# MODULO2_pp.net
KiCad netlist of a schematic drawn in EAGLE
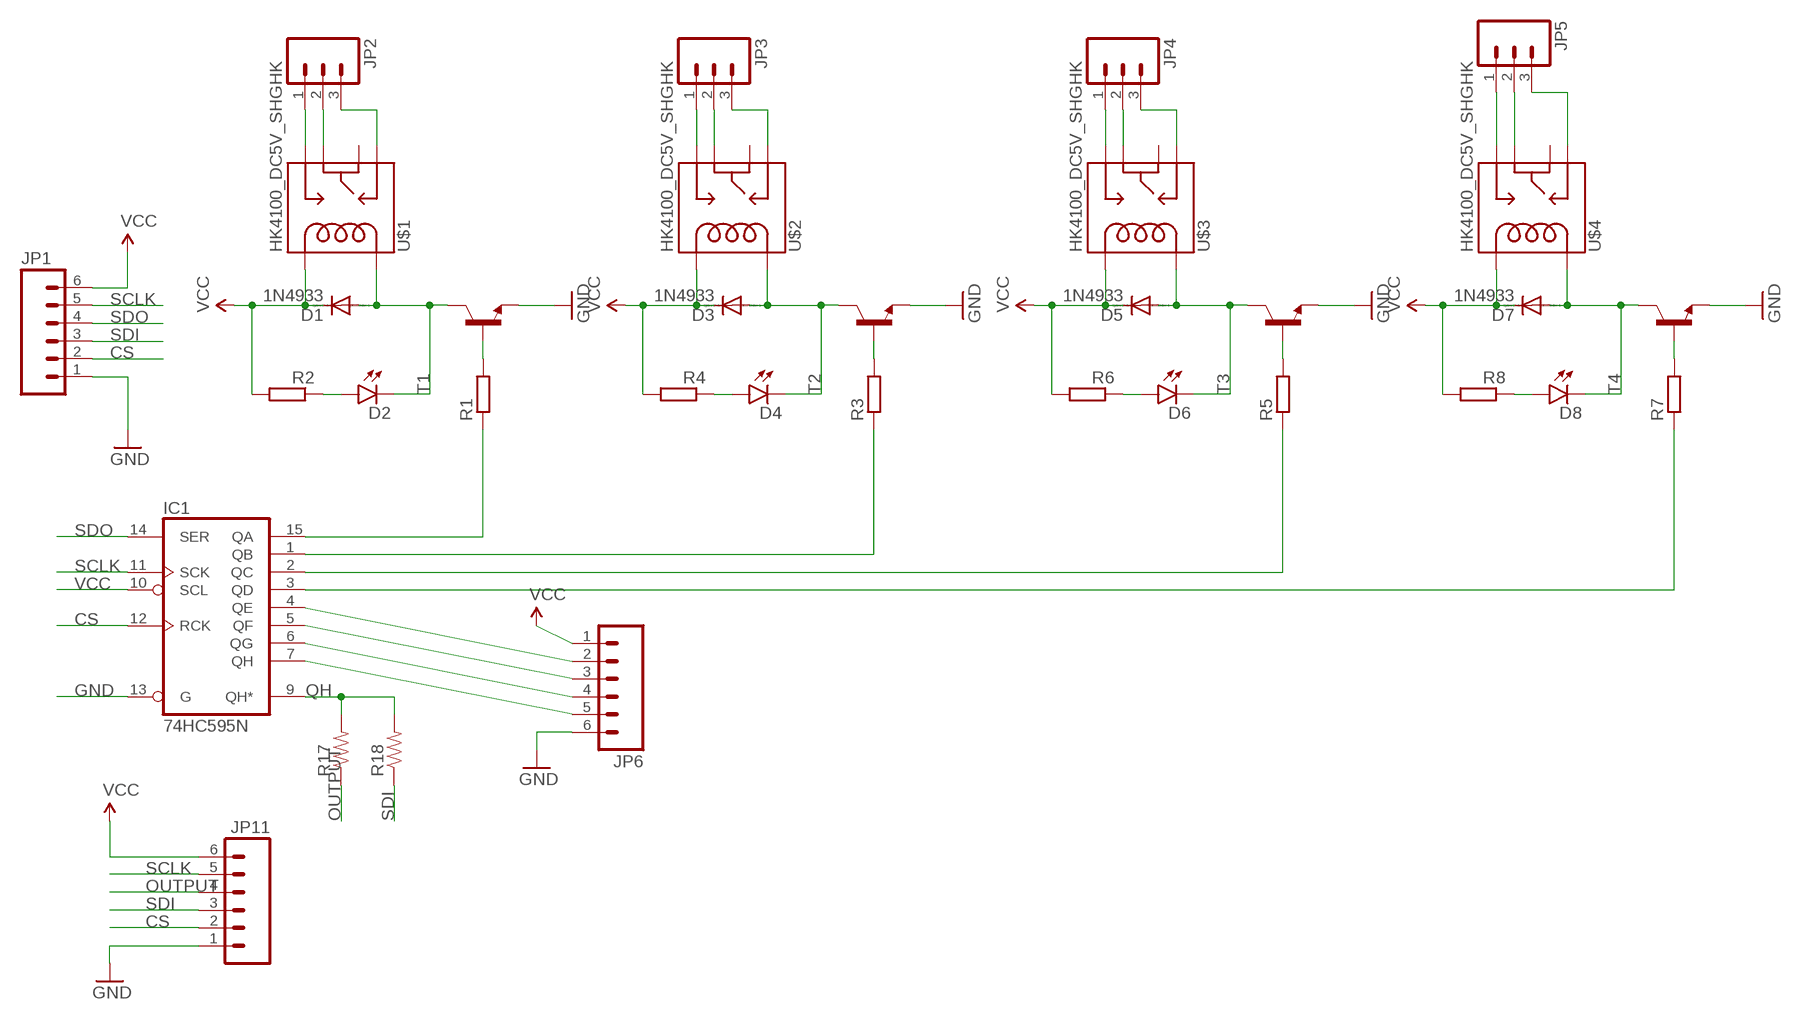
[diagram p0: schematic, sheet 1]

(export (version "E")
  (design (tool "Eeschema 10.0.6"))
  (components
    (comp (ref "D1")
      (value "1N4933")
      (footprint "eagle-import:DO41-10")
      (libsource (lib "eagle-import") (part "1N4933"))
    )
    (comp (ref "D2")
      (value "LED5MM")
      (footprint "eagle-import:LED5MM")
      (libsource (lib "eagle-import") (part "LED5MM"))
    )
    (comp (ref "D3")
      (value "1N4933")
      (footprint "eagle-import:DO41-10")
      (libsource (lib "eagle-import") (part "1N4933"))
    )
    (comp (ref "D4")
      (value "LED5MM")
      (footprint "eagle-import:LED5MM")
      (libsource (lib "eagle-import") (part "LED5MM"))
    )
    (comp (ref "D5")
      (value "1N4933")
      (footprint "eagle-import:DO41-10")
      (libsource (lib "eagle-import") (part "1N4933"))
    )
    (comp (ref "D6")
      (value "LED5MM")
      (footprint "eagle-import:LED5MM")
      (libsource (lib "eagle-import") (part "LED5MM"))
    )
    (comp (ref "D7")
      (value "1N4933")
      (footprint "eagle-import:DO41-10")
      (libsource (lib "eagle-import") (part "1N4933"))
    )
    (comp (ref "D8")
      (value "LED5MM")
      (footprint "eagle-import:LED5MM")
      (libsource (lib "eagle-import") (part "LED5MM"))
    )
    (comp (ref "IC1")
      (value "74HC595N")
      (footprint "eagle-import:DIL16")
      (libsource (lib "eagle-import") (part "74595NHC"))
    )
    (comp (ref "JP1")
      (value "M06SILK_FEMALE_PTH")
      (footprint "eagle-import:1X06")
      (libsource (lib "eagle-import") (part "M06SILK_FEMALE_PTH"))
    )
    (comp (ref "JP2")
      (value "M03-SCREW-5MM")
      (footprint "eagle-import:SCREWTERMINAL-5MM-3")
      (libsource (lib "eagle-import") (part "M03-SCREW-5MM"))
    )
    (comp (ref "JP3")
      (value "M03-SCREW-5MM")
      (footprint "eagle-import:SCREWTERMINAL-5MM-3")
      (libsource (lib "eagle-import") (part "M03-SCREW-5MM"))
    )
    (comp (ref "JP4")
      (value "M03-SCREW-5MM")
      (footprint "eagle-import:SCREWTERMINAL-5MM-3")
      (libsource (lib "eagle-import") (part "M03-SCREW-5MM"))
    )
    (comp (ref "JP5")
      (value "M03-SCREW-5MM")
      (footprint "eagle-import:SCREWTERMINAL-5MM-3")
      (libsource (lib "eagle-import") (part "M03-SCREW-5MM"))
    )
    (comp (ref "JP6")
      (value "M06SILK_FEMALE_PTH")
      (footprint "eagle-import:1X06")
      (libsource (lib "eagle-import") (part "M06SILK_FEMALE_PTH"))
    )
    (comp (ref "JP11")
      (value "M06SILK_FEMALE_PTH")
      (footprint "eagle-import:1X06")
      (libsource (lib "eagle-import") (part "M06SILK_FEMALE_PTH"))
    )
    (comp (ref "R1")
      (value "R-EU_R0805")
      (footprint "eagle-import:R0805")
      (libsource (lib "eagle-import") (part "R-EU_R0805"))
    )
    (comp (ref "R2")
      (value "R-EU_R0805")
      (footprint "eagle-import:R0805")
      (libsource (lib "eagle-import") (part "R-EU_R0805"))
    )
    (comp (ref "R3")
      (value "R-EU_R0805")
      (footprint "eagle-import:R0805")
      (libsource (lib "eagle-import") (part "R-EU_R0805"))
    )
    (comp (ref "R4")
      (value "R-EU_R0805")
      (footprint "eagle-import:R0805")
      (libsource (lib "eagle-import") (part "R-EU_R0805"))
    )
    (comp (ref "R5")
      (value "R-EU_R0805")
      (footprint "eagle-import:R0805")
      (libsource (lib "eagle-import") (part "R-EU_R0805"))
    )
    (comp (ref "R6")
      (value "R-EU_R0805")
      (footprint "eagle-import:R0805")
      (libsource (lib "eagle-import") (part "R-EU_R0805"))
    )
    (comp (ref "R7")
      (value "R-EU_R0805")
      (footprint "eagle-import:R0805")
      (libsource (lib "eagle-import") (part "R-EU_R0805"))
    )
    (comp (ref "R8")
      (value "R-EU_R0805")
      (footprint "eagle-import:R0805")
      (libsource (lib "eagle-import") (part "R-EU_R0805"))
    )
    (comp (ref "R17")
      (value "RESISTOR0805-RES")
      (footprint "eagle-import:0805")
      (libsource (lib "eagle-import") (part "RESISTOR0805-RES"))
    )
    (comp (ref "R18")
      (value "RESISTOR0805-RES")
      (footprint "eagle-import:0805")
      (libsource (lib "eagle-import") (part "RESISTOR0805-RES"))
    )
    (comp (ref "T1")
      (value "-NPN-TO92-EBC")
      (footprint "eagle-import:TO92-EBC")
      (libsource (lib "eagle-import") (part "-NPN-TO92-EBC"))
    )
    (comp (ref "T2")
      (value "-NPN-TO92-EBC")
      (footprint "eagle-import:TO92-EBC")
      (libsource (lib "eagle-import") (part "-NPN-TO92-EBC"))
    )
    (comp (ref "T3")
      (value "-NPN-TO92-EBC")
      (footprint "eagle-import:TO92-EBC")
      (libsource (lib "eagle-import") (part "-NPN-TO92-EBC"))
    )
    (comp (ref "T4")
      (value "-NPN-TO92-EBC")
      (footprint "eagle-import:TO92-EBC")
      (libsource (lib "eagle-import") (part "-NPN-TO92-EBC"))
    )
    (comp (ref "U$1")
      (value "HK4100_DC5V_SHGHK")
      (footprint "eagle-import:HK4100")
      (libsource (lib "eagle-import") (part "HK4100_DC5V_SHGHK"))
    )
    (comp (ref "U$2")
      (value "HK4100_DC5V_SHGHK")
      (footprint "eagle-import:HK4100")
      (libsource (lib "eagle-import") (part "HK4100_DC5V_SHGHK"))
    )
    (comp (ref "U$3")
      (value "HK4100_DC5V_SHGHK")
      (footprint "eagle-import:HK4100")
      (libsource (lib "eagle-import") (part "HK4100_DC5V_SHGHK"))
    )
    (comp (ref "U$4")
      (value "HK4100_DC5V_SHGHK")
      (footprint "eagle-import:HK4100")
      (libsource (lib "eagle-import") (part "HK4100_DC5V_SHGHK"))
    )
  )
  (nets
    (net (code "1") (name "/CS") (class "Default")
      (node (ref "IC1") (pin "12") (pinfunction "RCK_12") (pintype "input"))
      (node (ref "JP1") (pin "2") (pinfunction "2_2") (pintype "passive"))
      (node (ref "JP11") (pin "2") (pinfunction "2_2") (pintype "passive"))
    )
    (net (code "2") (name "/OUTPUT") (class "Default")
      (node (ref "JP11") (pin "4") (pinfunction "4_4") (pintype "passive"))
      (node (ref "R17") (pin "1") (pinfunction "1_1") (pintype "passive"))
    )
    (net (code "3") (name "/QH") (class "Default")
      (node (ref "IC1") (pin "9") (pinfunction "QH*_9") (pintype "tri_state"))
      (node (ref "R17") (pin "2") (pinfunction "2_2") (pintype "passive"))
      (node (ref "R18") (pin "2") (pinfunction "2_2") (pintype "passive"))
    )
    (net (code "4") (name "/SCLK") (class "Default")
      (node (ref "IC1") (pin "11") (pinfunction "SCK_11") (pintype "input"))
      (node (ref "JP1") (pin "5") (pinfunction "5_5") (pintype "passive"))
      (node (ref "JP11") (pin "5") (pinfunction "5_5") (pintype "passive"))
    )
    (net (code "5") (name "/SDI") (class "Default")
      (node (ref "JP1") (pin "3") (pinfunction "3_3") (pintype "passive"))
      (node (ref "JP11") (pin "3") (pinfunction "3_3") (pintype "passive"))
      (node (ref "R18") (pin "1") (pinfunction "1_1") (pintype "passive"))
    )
    (net (code "6") (name "/SDO") (class "Default")
      (node (ref "IC1") (pin "14") (pinfunction "SER_14") (pintype "input"))
      (node (ref "JP1") (pin "4") (pinfunction "4_4") (pintype "passive"))
    )
    (net (code "7") (name "GND") (class "Default")
      (node (ref "IC1") (pin "13") (pinfunction "G_13") (pintype "input"))
      (node (ref "JP1") (pin "1") (pinfunction "1_1") (pintype "passive"))
      (node (ref "JP11") (pin "1") (pinfunction "1_1") (pintype "passive"))
      (node (ref "JP6") (pin "6") (pinfunction "6_6") (pintype "passive"))
      (node (ref "T1") (pin "E") (pinfunction "E_E") (pintype "passive"))
      (node (ref "T2") (pin "E") (pinfunction "E_E") (pintype "passive"))
      (node (ref "T3") (pin "E") (pinfunction "E_E") (pintype "passive"))
      (node (ref "T4") (pin "E") (pinfunction "E_E") (pintype "passive"))
    )
    (net (code "8") (name "Net-(D2-C)") (class "Default")
      (node (ref "D1") (pin "A") (pinfunction "A_A") (pintype "passive"))
      (node (ref "D2") (pin "K") (pinfunction "C_K") (pintype "passive"))
      (node (ref "T1") (pin "C") (pinfunction "C_C") (pintype "passive"))
      (node (ref "U$1") (pin "6") (pinfunction "2_6") (pintype "bidirectional"))
    )
    (net (code "9") (name "Net-(D2-PadA)") (class "Default")
      (node (ref "D2") (pin "A") (pinfunction "A_A") (pintype "passive"))
      (node (ref "R2") (pin "1") (pinfunction "1_1") (pintype "passive"))
    )
    (net (code "10") (name "Net-(D4-C)") (class "Default")
      (node (ref "D3") (pin "A") (pinfunction "A_A") (pintype "passive"))
      (node (ref "D4") (pin "K") (pinfunction "C_K") (pintype "passive"))
      (node (ref "T2") (pin "C") (pinfunction "C_C") (pintype "passive"))
      (node (ref "U$2") (pin "6") (pinfunction "2_6") (pintype "bidirectional"))
    )
    (net (code "11") (name "Net-(D4-PadA)") (class "Default")
      (node (ref "D4") (pin "A") (pinfunction "A_A") (pintype "passive"))
      (node (ref "R4") (pin "1") (pinfunction "1_1") (pintype "passive"))
    )
    (net (code "12") (name "Net-(D6-C)") (class "Default")
      (node (ref "D5") (pin "A") (pinfunction "A_A") (pintype "passive"))
      (node (ref "D6") (pin "K") (pinfunction "C_K") (pintype "passive"))
      (node (ref "T3") (pin "C") (pinfunction "C_C") (pintype "passive"))
      (node (ref "U$3") (pin "6") (pinfunction "2_6") (pintype "bidirectional"))
    )
    (net (code "13") (name "Net-(D6-PadA)") (class "Default")
      (node (ref "D6") (pin "A") (pinfunction "A_A") (pintype "passive"))
      (node (ref "R6") (pin "1") (pinfunction "1_1") (pintype "passive"))
    )
    (net (code "14") (name "Net-(D8-C)") (class "Default")
      (node (ref "D7") (pin "A") (pinfunction "A_A") (pintype "passive"))
      (node (ref "D8") (pin "K") (pinfunction "C_K") (pintype "passive"))
      (node (ref "T4") (pin "C") (pinfunction "C_C") (pintype "passive"))
      (node (ref "U$4") (pin "6") (pinfunction "2_6") (pintype "bidirectional"))
    )
    (net (code "15") (name "Net-(D8-PadA)") (class "Default")
      (node (ref "D8") (pin "A") (pinfunction "A_A") (pintype "passive"))
      (node (ref "R8") (pin "1") (pinfunction "1_1") (pintype "passive"))
    )
    (net (code "16") (name "Net-(IC1A-QA)") (class "Default")
      (node (ref "IC1") (pin "15") (pinfunction "QA_15") (pintype "tri_state"))
      (node (ref "R1") (pin "1") (pinfunction "1_1") (pintype "passive"))
    )
    (net (code "17") (name "Net-(IC1A-QB)") (class "Default")
      (node (ref "IC1") (pin "1") (pinfunction "QB_1") (pintype "tri_state"))
      (node (ref "R3") (pin "1") (pinfunction "1_1") (pintype "passive"))
    )
    (net (code "18") (name "Net-(IC1A-QC)") (class "Default")
      (node (ref "IC1") (pin "2") (pinfunction "QC_2") (pintype "tri_state"))
      (node (ref "R5") (pin "1") (pinfunction "1_1") (pintype "passive"))
    )
    (net (code "19") (name "Net-(IC1A-QD)") (class "Default")
      (node (ref "IC1") (pin "3") (pinfunction "QD_3") (pintype "tri_state"))
      (node (ref "R7") (pin "1") (pinfunction "1_1") (pintype "passive"))
    )
    (net (code "20") (name "Net-(IC1A-QE)") (class "Default")
      (node (ref "IC1") (pin "4") (pinfunction "QE_4") (pintype "tri_state"))
      (node (ref "JP6") (pin "2") (pinfunction "2_2") (pintype "passive"))
    )
    (net (code "21") (name "Net-(IC1A-QF)") (class "Default")
      (node (ref "IC1") (pin "5") (pinfunction "QF_5") (pintype "tri_state"))
      (node (ref "JP6") (pin "3") (pinfunction "3_3") (pintype "passive"))
    )
    (net (code "22") (name "Net-(IC1A-QG)") (class "Default")
      (node (ref "IC1") (pin "6") (pinfunction "QG_6") (pintype "tri_state"))
      (node (ref "JP6") (pin "4") (pinfunction "4_4") (pintype "passive"))
    )
    (net (code "23") (name "Net-(IC1A-QH)") (class "Default")
      (node (ref "IC1") (pin "7") (pinfunction "QH_7") (pintype "tri_state"))
      (node (ref "JP6") (pin "5") (pinfunction "5_5") (pintype "passive"))
    )
    (net (code "24") (name "Net-(R1-Pad2)") (class "Default")
      (node (ref "R1") (pin "2") (pinfunction "2_2") (pintype "passive"))
      (node (ref "T1") (pin "B") (pinfunction "B_B") (pintype "passive"))
    )
    (net (code "25") (name "Net-(R3-Pad2)") (class "Default")
      (node (ref "R3") (pin "2") (pinfunction "2_2") (pintype "passive"))
      (node (ref "T2") (pin "B") (pinfunction "B_B") (pintype "passive"))
    )
    (net (code "26") (name "Net-(R5-Pad2)") (class "Default")
      (node (ref "R5") (pin "2") (pinfunction "2_2") (pintype "passive"))
      (node (ref "T3") (pin "B") (pinfunction "B_B") (pintype "passive"))
    )
    (net (code "27") (name "Net-(R7-Pad2)") (class "Default")
      (node (ref "R7") (pin "2") (pinfunction "2_2") (pintype "passive"))
      (node (ref "T4") (pin "B") (pinfunction "B_B") (pintype "passive"))
    )
    (net (code "28") (name "Net-(U$1-1)") (class "Default")
      (node (ref "JP2") (pin "3") (pinfunction "3_3") (pintype "passive"))
      (node (ref "U$1") (pin "7") (pinfunction "1_7") (pintype "bidirectional"))
    )
    (net (code "29") (name "Net-(U$1-6)") (class "Default")
      (node (ref "JP2") (pin "2") (pinfunction "2_2") (pintype "passive"))
      (node (ref "U$1") (pin "14") (pinfunction "6_14") (pintype "bidirectional"))
    )
    (net (code "30") (name "Net-(U$1-10)") (class "Default")
      (node (ref "JP2") (pin "1") (pinfunction "1_1") (pintype "passive"))
      (node (ref "U$1") (pin "8") (pinfunction "10_8") (pintype "bidirectional"))
    )
    (net (code "31") (name "Net-(U$2-1)") (class "Default")
      (node (ref "JP3") (pin "3") (pinfunction "3_3") (pintype "passive"))
      (node (ref "U$2") (pin "7") (pinfunction "1_7") (pintype "bidirectional"))
    )
    (net (code "32") (name "Net-(U$2-6)") (class "Default")
      (node (ref "JP3") (pin "2") (pinfunction "2_2") (pintype "passive"))
      (node (ref "U$2") (pin "14") (pinfunction "6_14") (pintype "bidirectional"))
    )
    (net (code "33") (name "Net-(U$2-10)") (class "Default")
      (node (ref "JP3") (pin "1") (pinfunction "1_1") (pintype "passive"))
      (node (ref "U$2") (pin "8") (pinfunction "10_8") (pintype "bidirectional"))
    )
    (net (code "34") (name "Net-(U$3-1)") (class "Default")
      (node (ref "JP4") (pin "3") (pinfunction "3_3") (pintype "passive"))
      (node (ref "U$3") (pin "7") (pinfunction "1_7") (pintype "bidirectional"))
    )
    (net (code "35") (name "Net-(U$3-6)") (class "Default")
      (node (ref "JP4") (pin "2") (pinfunction "2_2") (pintype "passive"))
      (node (ref "U$3") (pin "14") (pinfunction "6_14") (pintype "bidirectional"))
    )
    (net (code "36") (name "Net-(U$3-10)") (class "Default")
      (node (ref "JP4") (pin "1") (pinfunction "1_1") (pintype "passive"))
      (node (ref "U$3") (pin "8") (pinfunction "10_8") (pintype "bidirectional"))
    )
    (net (code "37") (name "Net-(U$4-1)") (class "Default")
      (node (ref "JP5") (pin "3") (pinfunction "3_3") (pintype "passive"))
      (node (ref "U$4") (pin "7") (pinfunction "1_7") (pintype "bidirectional"))
    )
    (net (code "38") (name "Net-(U$4-6)") (class "Default")
      (node (ref "JP5") (pin "2") (pinfunction "2_2") (pintype "passive"))
      (node (ref "U$4") (pin "14") (pinfunction "6_14") (pintype "bidirectional"))
    )
    (net (code "39") (name "Net-(U$4-10)") (class "Default")
      (node (ref "JP5") (pin "1") (pinfunction "1_1") (pintype "passive"))
      (node (ref "U$4") (pin "8") (pinfunction "10_8") (pintype "bidirectional"))
    )
    (net (code "40") (name "VCC") (class "Default")
      (node (ref "D1") (pin "C") (pinfunction "C_C") (pintype "passive"))
      (node (ref "D3") (pin "C") (pinfunction "C_C") (pintype "passive"))
      (node (ref "D5") (pin "C") (pinfunction "C_C") (pintype "passive"))
      (node (ref "D7") (pin "C") (pinfunction "C_C") (pintype "passive"))
      (node (ref "IC1") (pin "10") (pinfunction "SCL_10") (pintype "input"))
      (node (ref "JP1") (pin "6") (pinfunction "6_6") (pintype "passive"))
      (node (ref "JP11") (pin "6") (pinfunction "6_6") (pintype "passive"))
      (node (ref "JP6") (pin "1") (pinfunction "1_1") (pintype "passive"))
      (node (ref "R2") (pin "2") (pinfunction "2_2") (pintype "passive"))
      (node (ref "R4") (pin "2") (pinfunction "2_2") (pintype "passive"))
      (node (ref "R6") (pin "2") (pinfunction "2_2") (pintype "passive"))
      (node (ref "R8") (pin "2") (pinfunction "2_2") (pintype "passive"))
      (node (ref "U$1") (pin "9") (pinfunction "9_9") (pintype "bidirectional"))
      (node (ref "U$2") (pin "9") (pinfunction "9_9") (pintype "bidirectional"))
      (node (ref "U$3") (pin "9") (pinfunction "9_9") (pintype "bidirectional"))
      (node (ref "U$4") (pin "9") (pinfunction "9_9") (pintype "bidirectional"))
    )
    (net (code "41") (name "unconnected-(U$1-5-Pad1)") (class "Default")
      (node (ref "U$1") (pin "1") (pinfunction "5_1") (pintype "bidirectional"))
    )
    (net (code "42") (name "unconnected-(U$2-5-Pad1)") (class "Default")
      (node (ref "U$2") (pin "1") (pinfunction "5_1") (pintype "bidirectional"))
    )
    (net (code "43") (name "unconnected-(U$3-5-Pad1)") (class "Default")
      (node (ref "U$3") (pin "1") (pinfunction "5_1") (pintype "bidirectional"))
    )
    (net (code "44") (name "unconnected-(U$4-5-Pad1)") (class "Default")
      (node (ref "U$4") (pin "1") (pinfunction "5_1") (pintype "bidirectional"))
    )
  )
)
